# relay-set-d-large-block.net
KiCad netlist of a schematic drawn in EAGLE
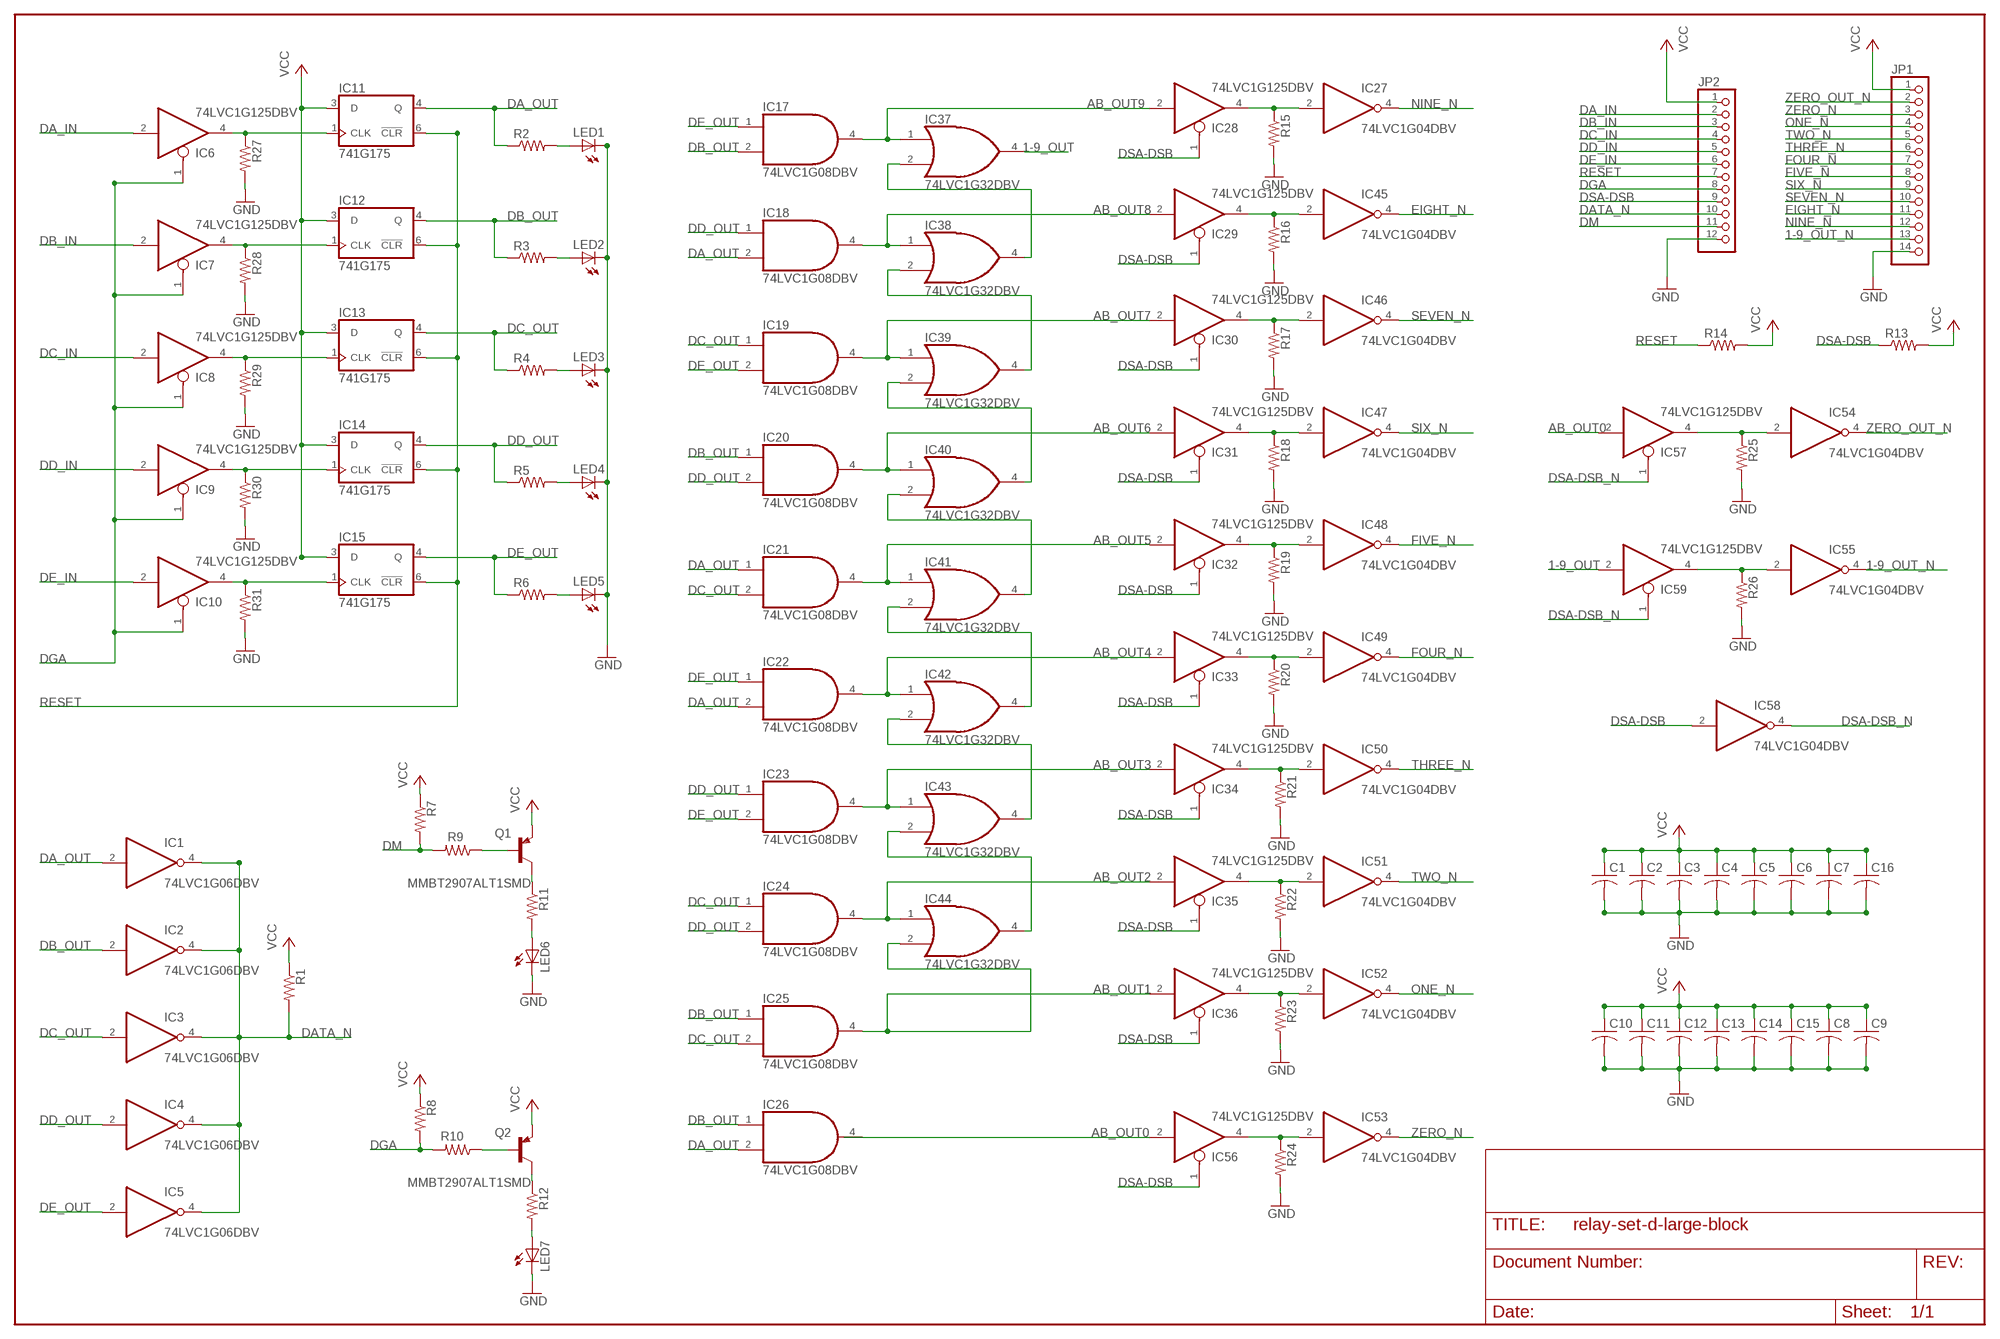
[diagram p0: schematic, sheet 1]

(export (version "E")
  (design (tool "Eeschema 10.0.6"))
  (components
    (comp (ref "C1")
      (value "C-USC0805")
      (footprint "eagle-import:C0805")
      (libsource (lib "eagle-import") (part "C-USC0805"))
    )
    (comp (ref "C2")
      (value "C-USC0805")
      (footprint "eagle-import:C0805")
      (libsource (lib "eagle-import") (part "C-USC0805"))
    )
    (comp (ref "C3")
      (value "C-USC0805")
      (footprint "eagle-import:C0805")
      (libsource (lib "eagle-import") (part "C-USC0805"))
    )
    (comp (ref "C4")
      (value "C-USC0805")
      (footprint "eagle-import:C0805")
      (libsource (lib "eagle-import") (part "C-USC0805"))
    )
    (comp (ref "C5")
      (value "C-USC0805")
      (footprint "eagle-import:C0805")
      (libsource (lib "eagle-import") (part "C-USC0805"))
    )
    (comp (ref "C6")
      (value "C-USC0805")
      (footprint "eagle-import:C0805")
      (libsource (lib "eagle-import") (part "C-USC0805"))
    )
    (comp (ref "C7")
      (value "C-USC0805")
      (footprint "eagle-import:C0805")
      (libsource (lib "eagle-import") (part "C-USC0805"))
    )
    (comp (ref "C8")
      (value "C-USC0805")
      (footprint "eagle-import:C0805")
      (libsource (lib "eagle-import") (part "C-USC0805"))
    )
    (comp (ref "C9")
      (value "C-USC0805")
      (footprint "eagle-import:C0805")
      (libsource (lib "eagle-import") (part "C-USC0805"))
    )
    (comp (ref "C10")
      (value "C-USC0805")
      (footprint "eagle-import:C0805")
      (libsource (lib "eagle-import") (part "C-USC0805"))
    )
    (comp (ref "C11")
      (value "C-USC0805")
      (footprint "eagle-import:C0805")
      (libsource (lib "eagle-import") (part "C-USC0805"))
    )
    (comp (ref "C12")
      (value "C-USC0805")
      (footprint "eagle-import:C0805")
      (libsource (lib "eagle-import") (part "C-USC0805"))
    )
    (comp (ref "C13")
      (value "C-USC0805")
      (footprint "eagle-import:C0805")
      (libsource (lib "eagle-import") (part "C-USC0805"))
    )
    (comp (ref "C14")
      (value "C-USC0805")
      (footprint "eagle-import:C0805")
      (libsource (lib "eagle-import") (part "C-USC0805"))
    )
    (comp (ref "C15")
      (value "C-USC0805")
      (footprint "eagle-import:C0805")
      (libsource (lib "eagle-import") (part "C-USC0805"))
    )
    (comp (ref "C16")
      (value "C-USC0805")
      (footprint "eagle-import:C0805")
      (libsource (lib "eagle-import") (part "C-USC0805"))
    )
    (comp (ref "IC1")
      (value "74LVC1G06DBV")
      (footprint "eagle-import:SOT23-5")
      (libsource (lib "eagle-import") (part "741G06DBVAUC"))
    )
    (comp (ref "IC2")
      (value "74LVC1G06DBV")
      (footprint "eagle-import:SOT23-5")
      (libsource (lib "eagle-import") (part "741G06DBVAUC"))
    )
    (comp (ref "IC3")
      (value "74LVC1G06DBV")
      (footprint "eagle-import:SOT23-5")
      (libsource (lib "eagle-import") (part "741G06DBVAUC"))
    )
    (comp (ref "IC4")
      (value "74LVC1G06DBV")
      (footprint "eagle-import:SOT23-5")
      (libsource (lib "eagle-import") (part "741G06DBVAUC"))
    )
    (comp (ref "IC5")
      (value "74LVC1G06DBV")
      (footprint "eagle-import:SOT23-5")
      (libsource (lib "eagle-import") (part "741G06DBVAUC"))
    )
    (comp (ref "IC6")
      (value "74LVC1G125DBV")
      (footprint "eagle-import:SOT23-5")
      (libsource (lib "eagle-import") (part "741G125DBVLVC"))
    )
    (comp (ref "IC7")
      (value "74LVC1G125DBV")
      (footprint "eagle-import:SOT23-5")
      (libsource (lib "eagle-import") (part "741G125DBVLVC"))
    )
    (comp (ref "IC8")
      (value "74LVC1G125DBV")
      (footprint "eagle-import:SOT23-5")
      (libsource (lib "eagle-import") (part "741G125DBVLVC"))
    )
    (comp (ref "IC9")
      (value "74LVC1G125DBV")
      (footprint "eagle-import:SOT23-5")
      (libsource (lib "eagle-import") (part "741G125DBVLVC"))
    )
    (comp (ref "IC10")
      (value "74LVC1G125DBV")
      (footprint "eagle-import:SOT23-5")
      (libsource (lib "eagle-import") (part "741G125DBVLVC"))
    )
    (comp (ref "IC11")
      (value "741G175")
      (footprint "eagle-import:DBV_R-PDSO-G6")
      (libsource (lib "eagle-import") (part "741G175"))
    )
    (comp (ref "IC12")
      (value "741G175")
      (footprint "eagle-import:DBV_R-PDSO-G6")
      (libsource (lib "eagle-import") (part "741G175"))
    )
    (comp (ref "IC13")
      (value "741G175")
      (footprint "eagle-import:DBV_R-PDSO-G6")
      (libsource (lib "eagle-import") (part "741G175"))
    )
    (comp (ref "IC14")
      (value "741G175")
      (footprint "eagle-import:DBV_R-PDSO-G6")
      (libsource (lib "eagle-import") (part "741G175"))
    )
    (comp (ref "IC15")
      (value "741G175")
      (footprint "eagle-import:DBV_R-PDSO-G6")
      (libsource (lib "eagle-import") (part "741G175"))
    )
    (comp (ref "IC17")
      (value "74LVC1G08DBV")
      (footprint "eagle-import:SOT23-5")
      (libsource (lib "eagle-import") (part "741G08DBVLVC"))
    )
    (comp (ref "IC18")
      (value "74LVC1G08DBV")
      (footprint "eagle-import:SOT23-5")
      (libsource (lib "eagle-import") (part "741G08DBVLVC"))
    )
    (comp (ref "IC19")
      (value "74LVC1G08DBV")
      (footprint "eagle-import:SOT23-5")
      (libsource (lib "eagle-import") (part "741G08DBVLVC"))
    )
    (comp (ref "IC20")
      (value "74LVC1G08DBV")
      (footprint "eagle-import:SOT23-5")
      (libsource (lib "eagle-import") (part "741G08DBVLVC"))
    )
    (comp (ref "IC21")
      (value "74LVC1G08DBV")
      (footprint "eagle-import:SOT23-5")
      (libsource (lib "eagle-import") (part "741G08DBVLVC"))
    )
    (comp (ref "IC22")
      (value "74LVC1G08DBV")
      (footprint "eagle-import:SOT23-5")
      (libsource (lib "eagle-import") (part "741G08DBVLVC"))
    )
    (comp (ref "IC23")
      (value "74LVC1G08DBV")
      (footprint "eagle-import:SOT23-5")
      (libsource (lib "eagle-import") (part "741G08DBVLVC"))
    )
    (comp (ref "IC24")
      (value "74LVC1G08DBV")
      (footprint "eagle-import:SOT23-5")
      (libsource (lib "eagle-import") (part "741G08DBVLVC"))
    )
    (comp (ref "IC25")
      (value "74LVC1G08DBV")
      (footprint "eagle-import:SOT23-5")
      (libsource (lib "eagle-import") (part "741G08DBVLVC"))
    )
    (comp (ref "IC26")
      (value "74LVC1G08DBV")
      (footprint "eagle-import:SOT23-5")
      (libsource (lib "eagle-import") (part "741G08DBVLVC"))
    )
    (comp (ref "IC27")
      (value "74LVC1G04DBV")
      (footprint "eagle-import:SOT23-5")
      (libsource (lib "eagle-import") (part "741G04DBVLVC"))
    )
    (comp (ref "IC28")
      (value "74LVC1G125DBV")
      (footprint "eagle-import:SOT23-5")
      (libsource (lib "eagle-import") (part "741G125DBVLVC"))
    )
    (comp (ref "IC29")
      (value "74LVC1G125DBV")
      (footprint "eagle-import:SOT23-5")
      (libsource (lib "eagle-import") (part "741G125DBVLVC"))
    )
    (comp (ref "IC30")
      (value "74LVC1G125DBV")
      (footprint "eagle-import:SOT23-5")
      (libsource (lib "eagle-import") (part "741G125DBVLVC"))
    )
    (comp (ref "IC31")
      (value "74LVC1G125DBV")
      (footprint "eagle-import:SOT23-5")
      (libsource (lib "eagle-import") (part "741G125DBVLVC"))
    )
    (comp (ref "IC32")
      (value "74LVC1G125DBV")
      (footprint "eagle-import:SOT23-5")
      (libsource (lib "eagle-import") (part "741G125DBVLVC"))
    )
    (comp (ref "IC33")
      (value "74LVC1G125DBV")
      (footprint "eagle-import:SOT23-5")
      (libsource (lib "eagle-import") (part "741G125DBVLVC"))
    )
    (comp (ref "IC34")
      (value "74LVC1G125DBV")
      (footprint "eagle-import:SOT23-5")
      (libsource (lib "eagle-import") (part "741G125DBVLVC"))
    )
    (comp (ref "IC35")
      (value "74LVC1G125DBV")
      (footprint "eagle-import:SOT23-5")
      (libsource (lib "eagle-import") (part "741G125DBVLVC"))
    )
    (comp (ref "IC36")
      (value "74LVC1G125DBV")
      (footprint "eagle-import:SOT23-5")
      (libsource (lib "eagle-import") (part "741G125DBVLVC"))
    )
    (comp (ref "IC37")
      (value "74LVC1G32DBV")
      (footprint "eagle-import:SOT23-5")
      (libsource (lib "eagle-import") (part "741G32DBVAHC"))
    )
    (comp (ref "IC38")
      (value "74LVC1G32DBV")
      (footprint "eagle-import:SOT23-5")
      (libsource (lib "eagle-import") (part "741G32DBVAHC"))
    )
    (comp (ref "IC39")
      (value "74LVC1G32DBV")
      (footprint "eagle-import:SOT23-5")
      (libsource (lib "eagle-import") (part "741G32DBVAHC"))
    )
    (comp (ref "IC40")
      (value "74LVC1G32DBV")
      (footprint "eagle-import:SOT23-5")
      (libsource (lib "eagle-import") (part "741G32DBVAHC"))
    )
    (comp (ref "IC41")
      (value "74LVC1G32DBV")
      (footprint "eagle-import:SOT23-5")
      (libsource (lib "eagle-import") (part "741G32DBVAHC"))
    )
    (comp (ref "IC42")
      (value "74LVC1G32DBV")
      (footprint "eagle-import:SOT23-5")
      (libsource (lib "eagle-import") (part "741G32DBVAHC"))
    )
    (comp (ref "IC43")
      (value "74LVC1G32DBV")
      (footprint "eagle-import:SOT23-5")
      (libsource (lib "eagle-import") (part "741G32DBVAHC"))
    )
    (comp (ref "IC44")
      (value "74LVC1G32DBV")
      (footprint "eagle-import:SOT23-5")
      (libsource (lib "eagle-import") (part "741G32DBVAHC"))
    )
    (comp (ref "IC45")
      (value "74LVC1G04DBV")
      (footprint "eagle-import:SOT23-5")
      (libsource (lib "eagle-import") (part "741G04DBVLVC"))
    )
    (comp (ref "IC46")
      (value "74LVC1G04DBV")
      (footprint "eagle-import:SOT23-5")
      (libsource (lib "eagle-import") (part "741G04DBVLVC"))
    )
    (comp (ref "IC47")
      (value "74LVC1G04DBV")
      (footprint "eagle-import:SOT23-5")
      (libsource (lib "eagle-import") (part "741G04DBVLVC"))
    )
    (comp (ref "IC48")
      (value "74LVC1G04DBV")
      (footprint "eagle-import:SOT23-5")
      (libsource (lib "eagle-import") (part "741G04DBVLVC"))
    )
    (comp (ref "IC49")
      (value "74LVC1G04DBV")
      (footprint "eagle-import:SOT23-5")
      (libsource (lib "eagle-import") (part "741G04DBVLVC"))
    )
    (comp (ref "IC50")
      (value "74LVC1G04DBV")
      (footprint "eagle-import:SOT23-5")
      (libsource (lib "eagle-import") (part "741G04DBVLVC"))
    )
    (comp (ref "IC51")
      (value "74LVC1G04DBV")
      (footprint "eagle-import:SOT23-5")
      (libsource (lib "eagle-import") (part "741G04DBVLVC"))
    )
    (comp (ref "IC52")
      (value "74LVC1G04DBV")
      (footprint "eagle-import:SOT23-5")
      (libsource (lib "eagle-import") (part "741G04DBVLVC"))
    )
    (comp (ref "IC53")
      (value "74LVC1G04DBV")
      (footprint "eagle-import:SOT23-5")
      (libsource (lib "eagle-import") (part "741G04DBVLVC"))
    )
    (comp (ref "IC54")
      (value "74LVC1G04DBV")
      (footprint "eagle-import:SOT23-5")
      (libsource (lib "eagle-import") (part "741G04DBVLVC"))
    )
    (comp (ref "IC55")
      (value "74LVC1G04DBV")
      (footprint "eagle-import:SOT23-5")
      (libsource (lib "eagle-import") (part "741G04DBVLVC"))
    )
    (comp (ref "IC56")
      (value "74LVC1G125DBV")
      (footprint "eagle-import:SOT23-5")
      (libsource (lib "eagle-import") (part "741G125DBVLVC"))
    )
    (comp (ref "IC57")
      (value "74LVC1G125DBV")
      (footprint "eagle-import:SOT23-5")
      (libsource (lib "eagle-import") (part "741G125DBVLVC"))
    )
    (comp (ref "IC58")
      (value "74LVC1G04DBV")
      (footprint "eagle-import:SOT23-5")
      (libsource (lib "eagle-import") (part "741G04DBVLVC"))
    )
    (comp (ref "IC59")
      (value "74LVC1G125DBV")
      (footprint "eagle-import:SOT23-5")
      (libsource (lib "eagle-import") (part "741G125DBVLVC"))
    )
    (comp (ref "JP1")
      (value "PINHD-1X14")
      (footprint "eagle-import:1X14")
      (libsource (lib "eagle-import") (part "PINHD-1X14"))
    )
    (comp (ref "JP2")
      (value "PINHD-1X12")
      (footprint "eagle-import:1X12")
      (libsource (lib "eagle-import") (part "PINHD-1X12"))
    )
    (comp (ref "LED1")
      (value "LEDCHIP-LED0805")
      (footprint "eagle-import:CHIP-LED0805")
      (libsource (lib "eagle-import") (part "LEDCHIP-LED0805"))
    )
    (comp (ref "LED2")
      (value "LEDCHIP-LED0805")
      (footprint "eagle-import:CHIP-LED0805")
      (libsource (lib "eagle-import") (part "LEDCHIP-LED0805"))
    )
    (comp (ref "LED3")
      (value "LEDCHIP-LED0805")
      (footprint "eagle-import:CHIP-LED0805")
      (libsource (lib "eagle-import") (part "LEDCHIP-LED0805"))
    )
    (comp (ref "LED4")
      (value "LEDCHIP-LED0805")
      (footprint "eagle-import:CHIP-LED0805")
      (libsource (lib "eagle-import") (part "LEDCHIP-LED0805"))
    )
    (comp (ref "LED5")
      (value "LEDCHIP-LED0805")
      (footprint "eagle-import:CHIP-LED0805")
      (libsource (lib "eagle-import") (part "LEDCHIP-LED0805"))
    )
    (comp (ref "LED6")
      (value "LEDCHIP-LED0805")
      (footprint "eagle-import:CHIP-LED0805")
      (libsource (lib "eagle-import") (part "LEDCHIP-LED0805"))
    )
    (comp (ref "LED7")
      (value "LEDCHIP-LED0805")
      (footprint "eagle-import:CHIP-LED0805")
      (libsource (lib "eagle-import") (part "LEDCHIP-LED0805"))
    )
    (comp (ref "Q1")
      (value "MMBT2907ALT1SMD")
      (footprint "eagle-import:SOT23-BEC")
      (libsource (lib "eagle-import") (part "MMBT2907SMDALT1"))
    )
    (comp (ref "Q2")
      (value "MMBT2907ALT1SMD")
      (footprint "eagle-import:SOT23-BEC")
      (libsource (lib "eagle-import") (part "MMBT2907SMDALT1"))
    )
    (comp (ref "R1")
      (value "R-US_R0805")
      (footprint "eagle-import:R0805")
      (libsource (lib "eagle-import") (part "R-US_R0805"))
    )
    (comp (ref "R2")
      (value "R-US_R0805")
      (footprint "eagle-import:R0805")
      (libsource (lib "eagle-import") (part "R-US_R0805"))
    )
    (comp (ref "R3")
      (value "R-US_R0805")
      (footprint "eagle-import:R0805")
      (libsource (lib "eagle-import") (part "R-US_R0805"))
    )
    (comp (ref "R4")
      (value "R-US_R0805")
      (footprint "eagle-import:R0805")
      (libsource (lib "eagle-import") (part "R-US_R0805"))
    )
    (comp (ref "R5")
      (value "R-US_R0805")
      (footprint "eagle-import:R0805")
      (libsource (lib "eagle-import") (part "R-US_R0805"))
    )
    (comp (ref "R6")
      (value "R-US_R0805")
      (footprint "eagle-import:R0805")
      (libsource (lib "eagle-import") (part "R-US_R0805"))
    )
    (comp (ref "R7")
      (value "R-US_R0805")
      (footprint "eagle-import:R0805")
      (libsource (lib "eagle-import") (part "R-US_R0805"))
    )
    (comp (ref "R8")
      (value "R-US_R0805")
      (footprint "eagle-import:R0805")
      (libsource (lib "eagle-import") (part "R-US_R0805"))
    )
    (comp (ref "R9")
      (value "R-US_R0805")
      (footprint "eagle-import:R0805")
      (libsource (lib "eagle-import") (part "R-US_R0805"))
    )
    (comp (ref "R10")
      (value "R-US_R0805")
      (footprint "eagle-import:R0805")
      (libsource (lib "eagle-import") (part "R-US_R0805"))
    )
    (comp (ref "R11")
      (value "R-US_R0805")
      (footprint "eagle-import:R0805")
      (libsource (lib "eagle-import") (part "R-US_R0805"))
    )
    (comp (ref "R12")
      (value "R-US_R0805")
      (footprint "eagle-import:R0805")
      (libsource (lib "eagle-import") (part "R-US_R0805"))
    )
    (comp (ref "R13")
      (value "R-US_R0805")
      (footprint "eagle-import:R0805")
      (libsource (lib "eagle-import") (part "R-US_R0805"))
    )
    (comp (ref "R14")
      (value "R-US_R0805")
      (footprint "eagle-import:R0805")
      (libsource (lib "eagle-import") (part "R-US_R0805"))
    )
    (comp (ref "R15")
      (value "R-US_R0805")
      (footprint "eagle-import:R0805")
      (libsource (lib "eagle-import") (part "R-US_R0805"))
    )
    (comp (ref "R16")
      (value "R-US_R0805")
      (footprint "eagle-import:R0805")
      (libsource (lib "eagle-import") (part "R-US_R0805"))
    )
    (comp (ref "R17")
      (value "R-US_R0805")
      (footprint "eagle-import:R0805")
      (libsource (lib "eagle-import") (part "R-US_R0805"))
    )
    (comp (ref "R18")
      (value "R-US_R0805")
      (footprint "eagle-import:R0805")
      (libsource (lib "eagle-import") (part "R-US_R0805"))
    )
    (comp (ref "R19")
      (value "R-US_R0805")
      (footprint "eagle-import:R0805")
      (libsource (lib "eagle-import") (part "R-US_R0805"))
    )
    (comp (ref "R20")
      (value "R-US_R0805")
      (footprint "eagle-import:R0805")
      (libsource (lib "eagle-import") (part "R-US_R0805"))
    )
    (comp (ref "R21")
      (value "R-US_R0805")
      (footprint "eagle-import:R0805")
      (libsource (lib "eagle-import") (part "R-US_R0805"))
    )
    (comp (ref "R22")
      (value "R-US_R0805")
      (footprint "eagle-import:R0805")
      (libsource (lib "eagle-import") (part "R-US_R0805"))
    )
    (comp (ref "R23")
      (value "R-US_R0805")
      (footprint "eagle-import:R0805")
      (libsource (lib "eagle-import") (part "R-US_R0805"))
    )
    (comp (ref "R24")
      (value "R-US_R0805")
      (footprint "eagle-import:R0805")
      (libsource (lib "eagle-import") (part "R-US_R0805"))
    )
    (comp (ref "R25")
      (value "R-US_R0805")
      (footprint "eagle-import:R0805")
      (libsource (lib "eagle-import") (part "R-US_R0805"))
    )
    (comp (ref "R26")
      (value "R-US_R0805")
      (footprint "eagle-import:R0805")
      (libsource (lib "eagle-import") (part "R-US_R0805"))
    )
    (comp (ref "R27")
      (value "R-US_R0805")
      (footprint "eagle-import:R0805")
      (libsource (lib "eagle-import") (part "R-US_R0805"))
    )
    (comp (ref "R28")
      (value "R-US_R0805")
      (footprint "eagle-import:R0805")
      (libsource (lib "eagle-import") (part "R-US_R0805"))
    )
    (comp (ref "R29")
      (value "R-US_R0805")
      (footprint "eagle-import:R0805")
      (libsource (lib "eagle-import") (part "R-US_R0805"))
    )
    (comp (ref "R30")
      (value "R-US_R0805")
      (footprint "eagle-import:R0805")
      (libsource (lib "eagle-import") (part "R-US_R0805"))
    )
    (comp (ref "R31")
      (value "R-US_R0805")
      (footprint "eagle-import:R0805")
      (libsource (lib "eagle-import") (part "R-US_R0805"))
    )
  )
  (nets
    (net (code "1") (name "/1-9_OUT") (class "Default")
      (node (ref "IC37") (pin "4") (pinfunction "O_4") (pintype "output"))
      (node (ref "IC59") (pin "2") (pinfunction "I_2") (pintype "input"))
    )
    (net (code "2") (name "/1-9_OUT_N") (class "Default")
      (node (ref "IC55") (pin "4") (pinfunction "O_4") (pintype "output"))
      (node (ref "JP1") (pin "13") (pinfunction "13_13") (pintype "passive"))
    )
    (net (code "3") (name "/AB_OUT0") (class "Default")
      (node (ref "IC56") (pin "2") (pinfunction "I_2") (pintype "input"))
      (node (ref "IC57") (pin "2") (pinfunction "I_2") (pintype "input"))
    )
    (net (code "4") (name "/AB_OUT1") (class "Default")
      (node (ref "IC25") (pin "4") (pinfunction "O_4") (pintype "output"))
      (node (ref "IC36") (pin "2") (pinfunction "I_2") (pintype "input"))
      (node (ref "IC44") (pin "2") (pinfunction "I1_2") (pintype "input"))
    )
    (net (code "5") (name "/AB_OUT2") (class "Default")
      (node (ref "IC24") (pin "4") (pinfunction "O_4") (pintype "output"))
      (node (ref "IC35") (pin "2") (pinfunction "I_2") (pintype "input"))
      (node (ref "IC44") (pin "1") (pinfunction "I0_1") (pintype "input"))
    )
    (net (code "6") (name "/AB_OUT3") (class "Default")
      (node (ref "IC23") (pin "4") (pinfunction "O_4") (pintype "output"))
      (node (ref "IC34") (pin "2") (pinfunction "I_2") (pintype "input"))
      (node (ref "IC43") (pin "1") (pinfunction "I0_1") (pintype "input"))
    )
    (net (code "7") (name "/AB_OUT4") (class "Default")
      (node (ref "IC22") (pin "4") (pinfunction "O_4") (pintype "output"))
      (node (ref "IC33") (pin "2") (pinfunction "I_2") (pintype "input"))
      (node (ref "IC42") (pin "1") (pinfunction "I0_1") (pintype "input"))
    )
    (net (code "8") (name "/AB_OUT5") (class "Default")
      (node (ref "IC21") (pin "4") (pinfunction "O_4") (pintype "output"))
      (node (ref "IC32") (pin "2") (pinfunction "I_2") (pintype "input"))
      (node (ref "IC41") (pin "1") (pinfunction "I0_1") (pintype "input"))
    )
    (net (code "9") (name "/AB_OUT6") (class "Default")
      (node (ref "IC20") (pin "4") (pinfunction "O_4") (pintype "output"))
      (node (ref "IC31") (pin "2") (pinfunction "I_2") (pintype "input"))
      (node (ref "IC40") (pin "1") (pinfunction "I0_1") (pintype "input"))
    )
    (net (code "10") (name "/AB_OUT7") (class "Default")
      (node (ref "IC19") (pin "4") (pinfunction "O_4") (pintype "output"))
      (node (ref "IC30") (pin "2") (pinfunction "I_2") (pintype "input"))
      (node (ref "IC39") (pin "1") (pinfunction "I0_1") (pintype "input"))
    )
    (net (code "11") (name "/AB_OUT8") (class "Default")
      (node (ref "IC18") (pin "4") (pinfunction "O_4") (pintype "output"))
      (node (ref "IC29") (pin "2") (pinfunction "I_2") (pintype "input"))
      (node (ref "IC38") (pin "1") (pinfunction "I0_1") (pintype "input"))
    )
    (net (code "12") (name "/AB_OUT9") (class "Default")
      (node (ref "IC17") (pin "4") (pinfunction "O_4") (pintype "output"))
      (node (ref "IC28") (pin "2") (pinfunction "I_2") (pintype "input"))
      (node (ref "IC37") (pin "1") (pinfunction "I0_1") (pintype "input"))
    )
    (net (code "13") (name "/DATA_N") (class "Default")
      (node (ref "IC1") (pin "4") (pinfunction "O_4") (pintype "open_collector"))
      (node (ref "IC2") (pin "4") (pinfunction "O_4") (pintype "open_collector"))
      (node (ref "IC3") (pin "4") (pinfunction "O_4") (pintype "open_collector"))
      (node (ref "IC4") (pin "4") (pinfunction "O_4") (pintype "open_collector"))
      (node (ref "IC5") (pin "4") (pinfunction "O_4") (pintype "open_collector"))
      (node (ref "JP2") (pin "10") (pinfunction "10_10") (pintype "passive"))
      (node (ref "R1") (pin "2") (pinfunction "2_2") (pintype "passive"))
    )
    (net (code "14") (name "/DA_IN") (class "Default")
      (node (ref "IC6") (pin "2") (pinfunction "I_2") (pintype "input"))
      (node (ref "JP2") (pin "2") (pinfunction "2_2") (pintype "passive"))
    )
    (net (code "15") (name "/DA_OUT") (class "Default")
      (node (ref "IC1") (pin "2") (pinfunction "I_2") (pintype "input"))
      (node (ref "IC11") (pin "4") (pinfunction "Q_4") (pintype "output"))
      (node (ref "IC18") (pin "2") (pinfunction "I1_2") (pintype "input"))
      (node (ref "IC21") (pin "1") (pinfunction "I0_1") (pintype "input"))
      (node (ref "IC22") (pin "2") (pinfunction "I1_2") (pintype "input"))
      (node (ref "IC26") (pin "2") (pinfunction "I1_2") (pintype "input"))
      (node (ref "R2") (pin "1") (pinfunction "1_1") (pintype "passive"))
    )
    (net (code "16") (name "/DB_IN") (class "Default")
      (node (ref "IC7") (pin "2") (pinfunction "I_2") (pintype "input"))
      (node (ref "JP2") (pin "3") (pinfunction "3_3") (pintype "passive"))
    )
    (net (code "17") (name "/DB_OUT") (class "Default")
      (node (ref "IC12") (pin "4") (pinfunction "Q_4") (pintype "output"))
      (node (ref "IC17") (pin "2") (pinfunction "I1_2") (pintype "input"))
      (node (ref "IC2") (pin "2") (pinfunction "I_2") (pintype "input"))
      (node (ref "IC20") (pin "1") (pinfunction "I0_1") (pintype "input"))
      (node (ref "IC25") (pin "1") (pinfunction "I0_1") (pintype "input"))
      (node (ref "IC26") (pin "1") (pinfunction "I0_1") (pintype "input"))
      (node (ref "R3") (pin "1") (pinfunction "1_1") (pintype "passive"))
    )
    (net (code "18") (name "/DC_IN") (class "Default")
      (node (ref "IC8") (pin "2") (pinfunction "I_2") (pintype "input"))
      (node (ref "JP2") (pin "4") (pinfunction "4_4") (pintype "passive"))
    )
    (net (code "19") (name "/DC_OUT") (class "Default")
      (node (ref "IC13") (pin "4") (pinfunction "Q_4") (pintype "output"))
      (node (ref "IC19") (pin "1") (pinfunction "I0_1") (pintype "input"))
      (node (ref "IC21") (pin "2") (pinfunction "I1_2") (pintype "input"))
      (node (ref "IC24") (pin "1") (pinfunction "I0_1") (pintype "input"))
      (node (ref "IC25") (pin "2") (pinfunction "I1_2") (pintype "input"))
      (node (ref "IC3") (pin "2") (pinfunction "I_2") (pintype "input"))
      (node (ref "R4") (pin "1") (pinfunction "1_1") (pintype "passive"))
    )
    (net (code "20") (name "/DD_IN") (class "Default")
      (node (ref "IC9") (pin "2") (pinfunction "I_2") (pintype "input"))
      (node (ref "JP2") (pin "5") (pinfunction "5_5") (pintype "passive"))
    )
    (net (code "21") (name "/DD_OUT") (class "Default")
      (node (ref "IC14") (pin "4") (pinfunction "Q_4") (pintype "output"))
      (node (ref "IC18") (pin "1") (pinfunction "I0_1") (pintype "input"))
      (node (ref "IC20") (pin "2") (pinfunction "I1_2") (pintype "input"))
      (node (ref "IC23") (pin "1") (pinfunction "I0_1") (pintype "input"))
      (node (ref "IC24") (pin "2") (pinfunction "I1_2") (pintype "input"))
      (node (ref "IC4") (pin "2") (pinfunction "I_2") (pintype "input"))
      (node (ref "R5") (pin "1") (pinfunction "1_1") (pintype "passive"))
    )
    (net (code "22") (name "/DE_IN") (class "Default")
      (node (ref "IC10") (pin "2") (pinfunction "I_2") (pintype "input"))
      (node (ref "JP2") (pin "6") (pinfunction "6_6") (pintype "passive"))
    )
    (net (code "23") (name "/DE_OUT") (class "Default")
      (node (ref "IC15") (pin "4") (pinfunction "Q_4") (pintype "output"))
      (node (ref "IC17") (pin "1") (pinfunction "I0_1") (pintype "input"))
      (node (ref "IC19") (pin "2") (pinfunction "I1_2") (pintype "input"))
      (node (ref "IC22") (pin "1") (pinfunction "I0_1") (pintype "input"))
      (node (ref "IC23") (pin "2") (pinfunction "I1_2") (pintype "input"))
      (node (ref "IC5") (pin "2") (pinfunction "I_2") (pintype "input"))
      (node (ref "R6") (pin "1") (pinfunction "1_1") (pintype "passive"))
    )
    (net (code "24") (name "/DGA") (class "Default")
      (node (ref "IC10") (pin "1") (pinfunction "OE_1") (pintype "input"))
      (node (ref "IC6") (pin "1") (pinfunction "OE_1") (pintype "input"))
      (node (ref "IC7") (pin "1") (pinfunction "OE_1") (pintype "input"))
      (node (ref "IC8") (pin "1") (pinfunction "OE_1") (pintype "input"))
      (node (ref "IC9") (pin "1") (pinfunction "OE_1") (pintype "input"))
      (node (ref "JP2") (pin "8") (pinfunction "8_8") (pintype "passive"))
      (node (ref "R10") (pin "2") (pinfunction "2_2") (pintype "passive"))
      (node (ref "R8") (pin "2") (pinfunction "2_2") (pintype "passive"))
    )
    (net (code "25") (name "/DM") (class "Default")
      (node (ref "JP2") (pin "11") (pinfunction "11_11") (pintype "passive"))
      (node (ref "R7") (pin "2") (pinfunction "2_2") (pintype "passive"))
      (node (ref "R9") (pin "2") (pinfunction "2_2") (pintype "passive"))
    )
    (net (code "26") (name "/DSA-DSB") (class "Default")
      (node (ref "IC28") (pin "1") (pinfunction "OE_1") (pintype "input"))
      (node (ref "IC29") (pin "1") (pinfunction "OE_1") (pintype "input"))
      (node (ref "IC30") (pin "1") (pinfunction "OE_1") (pintype "input"))
      (node (ref "IC31") (pin "1") (pinfunction "OE_1") (pintype "input"))
      (node (ref "IC32") (pin "1") (pinfunction "OE_1") (pintype "input"))
      (node (ref "IC33") (pin "1") (pinfunction "OE_1") (pintype "input"))
      (node (ref "IC34") (pin "1") (pinfunction "OE_1") (pintype "input"))
      (node (ref "IC35") (pin "1") (pinfunction "OE_1") (pintype "input"))
      (node (ref "IC36") (pin "1") (pinfunction "OE_1") (pintype "input"))
      (node (ref "IC56") (pin "1") (pinfunction "OE_1") (pintype "input"))
      (node (ref "IC58") (pin "2") (pinfunction "I_2") (pintype "input"))
      (node (ref "JP2") (pin "9") (pinfunction "9_9") (pintype "passive"))
      (node (ref "R13") (pin "1") (pinfunction "1_1") (pintype "passive"))
    )
    (net (code "27") (name "/DSA-DSB_N") (class "Default")
      (node (ref "IC57") (pin "1") (pinfunction "OE_1") (pintype "input"))
      (node (ref "IC58") (pin "4") (pinfunction "O_4") (pintype "output"))
      (node (ref "IC59") (pin "1") (pinfunction "OE_1") (pintype "input"))
    )
    (net (code "28") (name "/EIGHT_N") (class "Default")
      (node (ref "IC45") (pin "4") (pinfunction "O_4") (pintype "output"))
      (node (ref "JP1") (pin "11") (pinfunction "11_11") (pintype "passive"))
    )
    (net (code "29") (name "/FIVE_N") (class "Default")
      (node (ref "IC48") (pin "4") (pinfunction "O_4") (pintype "output"))
      (node (ref "JP1") (pin "8") (pinfunction "8_8") (pintype "passive"))
    )
    (net (code "30") (name "/FOUR_N") (class "Default")
      (node (ref "IC49") (pin "4") (pinfunction "O_4") (pintype "output"))
      (node (ref "JP1") (pin "7") (pinfunction "7_7") (pintype "passive"))
    )
    (net (code "31") (name "/NINE_N") (class "Default")
      (node (ref "IC27") (pin "4") (pinfunction "O_4") (pintype "output"))
      (node (ref "JP1") (pin "12") (pinfunction "12_12") (pintype "passive"))
    )
    (net (code "32") (name "/ONE_N") (class "Default")
      (node (ref "IC52") (pin "4") (pinfunction "O_4") (pintype "output"))
      (node (ref "JP1") (pin "4") (pinfunction "4_4") (pintype "passive"))
    )
    (net (code "33") (name "/RESET") (class "Default")
      (node (ref "IC11") (pin "6") (pinfunction "~{CLR}_6") (pintype "output"))
      (node (ref "IC12") (pin "6") (pinfunction "~{CLR}_6") (pintype "output"))
      (node (ref "IC13") (pin "6") (pinfunction "~{CLR}_6") (pintype "output"))
      (node (ref "IC14") (pin "6") (pinfunction "~{CLR}_6") (pintype "output"))
      (node (ref "IC15") (pin "6") (pinfunction "~{CLR}_6") (pintype "output"))
      (node (ref "JP2") (pin "7") (pinfunction "7_7") (pintype "passive"))
      (node (ref "R14") (pin "1") (pinfunction "1_1") (pintype "passive"))
    )
    (net (code "34") (name "/SEVEN_N") (class "Default")
      (node (ref "IC46") (pin "4") (pinfunction "O_4") (pintype "output"))
      (node (ref "JP1") (pin "10") (pinfunction "10_10") (pintype "passive"))
    )
    (net (code "35") (name "/SIX_N") (class "Default")
      (node (ref "IC47") (pin "4") (pinfunction "O_4") (pintype "output"))
      (node (ref "JP1") (pin "9") (pinfunction "9_9") (pintype "passive"))
    )
    (net (code "36") (name "/THREE_N") (class "Default")
      (node (ref "IC50") (pin "4") (pinfunction "O_4") (pintype "output"))
      (node (ref "JP1") (pin "6") (pinfunction "6_6") (pintype "passive"))
    )
    (net (code "37") (name "/TWO_N") (class "Default")
      (node (ref "IC51") (pin "4") (pinfunction "O_4") (pintype "output"))
      (node (ref "JP1") (pin "5") (pinfunction "5_5") (pintype "passive"))
    )
    (net (code "38") (name "/ZERO_N") (class "Default")
      (node (ref "IC53") (pin "4") (pinfunction "O_4") (pintype "output"))
      (node (ref "JP1") (pin "3") (pinfunction "3_3") (pintype "passive"))
    )
    (net (code "39") (name "/ZERO_OUT_N") (class "Default")
      (node (ref "IC54") (pin "4") (pinfunction "O_4") (pintype "output"))
      (node (ref "JP1") (pin "2") (pinfunction "2_2") (pintype "passive"))
    )
    (net (code "40") (name "GND") (class "Default")
      (node (ref "C1") (pin "2") (pinfunction "2_2") (pintype "passive"))
      (node (ref "C10") (pin "2") (pinfunction "2_2") (pintype "passive"))
      (node (ref "C11") (pin "2") (pinfunction "2_2") (pintype "passive"))
      (node (ref "C12") (pin "2") (pinfunction "2_2") (pintype "passive"))
      (node (ref "C13") (pin "2") (pinfunction "2_2") (pintype "passive"))
      (node (ref "C14") (pin "2") (pinfunction "2_2") (pintype "passive"))
      (node (ref "C15") (pin "2") (pinfunction "2_2") (pintype "passive"))
      (node (ref "C16") (pin "2") (pinfunction "2_2") (pintype "passive"))
      (node (ref "C2") (pin "2") (pinfunction "2_2") (pintype "passive"))
      (node (ref "C3") (pin "2") (pinfunction "2_2") (pintype "passive"))
      (node (ref "C4") (pin "2") (pinfunction "2_2") (pintype "passive"))
      (node (ref "C5") (pin "2") (pinfunction "2_2") (pintype "passive"))
      (node (ref "C6") (pin "2") (pinfunction "2_2") (pintype "passive"))
      (node (ref "C7") (pin "2") (pinfunction "2_2") (pintype "passive"))
      (node (ref "C8") (pin "2") (pinfunction "2_2") (pintype "passive"))
      (node (ref "C9") (pin "2") (pinfunction "2_2") (pintype "passive"))
      (node (ref "JP1") (pin "14") (pinfunction "14_14") (pintype "passive"))
      (node (ref "JP2") (pin "12") (pinfunction "12_12") (pintype "passive"))
      (node (ref "LED1") (pin "C") (pinfunction "C_C") (pintype "passive"))
      (node (ref "LED2") (pin "C") (pinfunction "C_C") (pintype "passive"))
      (node (ref "LED3") (pin "C") (pinfunction "C_C") (pintype "passive"))
      (node (ref "LED4") (pin "C") (pinfunction "C_C") (pintype "passive"))
      (node (ref "LED5") (pin "C") (pinfunction "C_C") (pintype "passive"))
      (node (ref "LED6") (pin "C") (pinfunction "C_C") (pintype "passive"))
      (node (ref "LED7") (pin "C") (pinfunction "C_C") (pintype "passive"))
      (node (ref "R15") (pin "2") (pinfunction "2_2") (pintype "passive"))
      (node (ref "R16") (pin "2") (pinfunction "2_2") (pintype "passive"))
      (node (ref "R17") (pin "2") (pinfunction "2_2") (pintype "passive"))
      (node (ref "R18") (pin "2") (pinfunction "2_2") (pintype "passive"))
      (node (ref "R19") (pin "2") (pinfunction "2_2") (pintype "passive"))
      (node (ref "R20") (pin "2") (pinfunction "2_2") (pintype "passive"))
      (node (ref "R21") (pin "2") (pinfunction "2_2") (pintype "passive"))
      (node (ref "R22") (pin "2") (pinfunction "2_2") (pintype "passive"))
      (node (ref "R23") (pin "2") (pinfunction "2_2") (pintype "passive"))
      (node (ref "R24") (pin "2") (pinfunction "2_2") (pintype "passive"))
      (node (ref "R25") (pin "2") (pinfunction "2_2") (pintype "passive"))
      (node (ref "R26") (pin "2") (pinfunction "2_2") (pintype "passive"))
      (node (ref "R27") (pin "2") (pinfunction "2_2") (pintype "passive"))
      (node (ref "R28") (pin "2") (pinfunction "2_2") (pintype "passive"))
      (node (ref "R29") (pin "2") (pinfunction "2_2") (pintype "passive"))
      (node (ref "R30") (pin "2") (pinfunction "2_2") (pintype "passive"))
      (node (ref "R31") (pin "2") (pinfunction "2_2") (pintype "passive"))
    )
    (net (code "41") (name "Net-(IC10A-O)") (class "Default")
      (node (ref "IC10") (pin "4") (pinfunction "O_4") (pintype "tri_state"))
      (node (ref "IC15") (pin "1") (pinfunction "CLK_1") (pintype "input"))
      (node (ref "R31") (pin "1") (pinfunction "1_1") (pintype "passive"))
    )
    (net (code "42") (name "Net-(IC11A-CLK)") (class "Default")
      (node (ref "IC11") (pin "1") (pinfunction "CLK_1") (pintype "input"))
      (node (ref "IC6") (pin "4") (pinfunction "O_4") (pintype "tri_state"))
      (node (ref "R27") (pin "1") (pinfunction "1_1") (pintype "passive"))
    )
    (net (code "43") (name "Net-(IC12A-CLK)") (class "Default")
      (node (ref "IC12") (pin "1") (pinfunction "CLK_1") (pintype "input"))
      (node (ref "IC7") (pin "4") (pinfunction "O_4") (pintype "tri_state"))
      (node (ref "R28") (pin "1") (pinfunction "1_1") (pintype "passive"))
    )
    (net (code "44") (name "Net-(IC13A-CLK)") (class "Default")
      (node (ref "IC13") (pin "1") (pinfunction "CLK_1") (pintype "input"))
      (node (ref "IC8") (pin "4") (pinfunction "O_4") (pintype "tri_state"))
      (node (ref "R29") (pin "1") (pinfunction "1_1") (pintype "passive"))
    )
    (net (code "45") (name "Net-(IC14A-CLK)") (class "Default")
      (node (ref "IC14") (pin "1") (pinfunction "CLK_1") (pintype "input"))
      (node (ref "IC9") (pin "4") (pinfunction "O_4") (pintype "tri_state"))
      (node (ref "R30") (pin "1") (pinfunction "1_1") (pintype "passive"))
    )
    (net (code "46") (name "Net-(IC27A-I)") (class "Default")
      (node (ref "IC27") (pin "2") (pinfunction "I_2") (pintype "input"))
      (node (ref "IC28") (pin "4") (pinfunction "O_4") (pintype "tri_state"))
      (node (ref "R15") (pin "1") (pinfunction "1_1") (pintype "passive"))
    )
    (net (code "47") (name "Net-(IC29A-O)") (class "Default")
      (node (ref "IC29") (pin "4") (pinfunction "O_4") (pintype "tri_state"))
      (node (ref "IC45") (pin "2") (pinfunction "I_2") (pintype "input"))
      (node (ref "R16") (pin "1") (pinfunction "1_1") (pintype "passive"))
    )
    (net (code "48") (name "Net-(IC30A-O)") (class "Default")
      (node (ref "IC30") (pin "4") (pinfunction "O_4") (pintype "tri_state"))
      (node (ref "IC46") (pin "2") (pinfunction "I_2") (pintype "input"))
      (node (ref "R17") (pin "1") (pinfunction "1_1") (pintype "passive"))
    )
    (net (code "49") (name "Net-(IC31A-O)") (class "Default")
      (node (ref "IC31") (pin "4") (pinfunction "O_4") (pintype "tri_state"))
      (node (ref "IC47") (pin "2") (pinfunction "I_2") (pintype "input"))
      (node (ref "R18") (pin "1") (pinfunction "1_1") (pintype "passive"))
    )
    (net (code "50") (name "Net-(IC32A-O)") (class "Default")
      (node (ref "IC32") (pin "4") (pinfunction "O_4") (pintype "tri_state"))
      (node (ref "IC48") (pin "2") (pinfunction "I_2") (pintype "input"))
      (node (ref "R19") (pin "1") (pinfunction "1_1") (pintype "passive"))
    )
    (net (code "51") (name "Net-(IC33A-O)") (class "Default")
      (node (ref "IC33") (pin "4") (pinfunction "O_4") (pintype "tri_state"))
      (node (ref "IC49") (pin "2") (pinfunction "I_2") (pintype "input"))
      (node (ref "R20") (pin "1") (pinfunction "1_1") (pintype "passive"))
    )
    (net (code "52") (name "Net-(IC34A-O)") (class "Default")
      (node (ref "IC34") (pin "4") (pinfunction "O_4") (pintype "tri_state"))
      (node (ref "IC50") (pin "2") (pinfunction "I_2") (pintype "input"))
      (node (ref "R21") (pin "1") (pinfunction "1_1") (pintype "passive"))
    )
    (net (code "53") (name "Net-(IC35A-O)") (class "Default")
      (node (ref "IC35") (pin "4") (pinfunction "O_4") (pintype "tri_state"))
      (node (ref "IC51") (pin "2") (pinfunction "I_2") (pintype "input"))
      (node (ref "R22") (pin "1") (pinfunction "1_1") (pintype "passive"))
    )
    (net (code "54") (name "Net-(IC36A-O)") (class "Default")
      (node (ref "IC36") (pin "4") (pinfunction "O_4") (pintype "tri_state"))
      (node (ref "IC52") (pin "2") (pinfunction "I_2") (pintype "input"))
      (node (ref "R23") (pin "1") (pinfunction "1_1") (pintype "passive"))
    )
    (net (code "55") (name "Net-(IC37A-I1)") (class "Default")
      (node (ref "IC37") (pin "2") (pinfunction "I1_2") (pintype "input"))
      (node (ref "IC38") (pin "4") (pinfunction "O_4") (pintype "output"))
    )
    (net (code "56") (name "Net-(IC38A-I1)") (class "Default")
      (node (ref "IC38") (pin "2") (pinfunction "I1_2") (pintype "input"))
      (node (ref "IC39") (pin "4") (pinfunction "O_4") (pintype "output"))
    )
    (net (code "57") (name "Net-(IC39A-I1)") (class "Default")
      (node (ref "IC39") (pin "2") (pinfunction "I1_2") (pintype "input"))
      (node (ref "IC40") (pin "4") (pinfunction "O_4") (pintype "output"))
    )
    (net (code "58") (name "Net-(IC40A-I1)") (class "Default")
      (node (ref "IC40") (pin "2") (pinfunction "I1_2") (pintype "input"))
      (node (ref "IC41") (pin "4") (pinfunction "O_4") (pintype "output"))
    )
    (net (code "59") (name "Net-(IC41A-I1)") (class "Default")
      (node (ref "IC41") (pin "2") (pinfunction "I1_2") (pintype "input"))
      (node (ref "IC42") (pin "4") (pinfunction "O_4") (pintype "output"))
    )
    (net (code "60") (name "Net-(IC42A-I1)") (class "Default")
      (node (ref "IC42") (pin "2") (pinfunction "I1_2") (pintype "input"))
      (node (ref "IC43") (pin "4") (pinfunction "O_4") (pintype "output"))
    )
    (net (code "61") (name "Net-(IC43A-I1)") (class "Default")
      (node (ref "IC43") (pin "2") (pinfunction "I1_2") (pintype "input"))
      (node (ref "IC44") (pin "4") (pinfunction "O_4") (pintype "output"))
    )
    (net (code "62") (name "Net-(IC53A-I)") (class "Default")
      (node (ref "IC53") (pin "2") (pinfunction "I_2") (pintype "input"))
      (node (ref "IC56") (pin "4") (pinfunction "O_4") (pintype "tri_state"))
      (node (ref "R24") (pin "1") (pinfunction "1_1") (pintype "passive"))
    )
    (net (code "63") (name "Net-(IC54A-I)") (class "Default")
      (node (ref "IC54") (pin "2") (pinfunction "I_2") (pintype "input"))
      (node (ref "IC57") (pin "4") (pinfunction "O_4") (pintype "tri_state"))
      (node (ref "R25") (pin "1") (pinfunction "1_1") (pintype "passive"))
    )
    (net (code "64") (name "Net-(IC55A-I)") (class "Default")
      (node (ref "IC55") (pin "2") (pinfunction "I_2") (pintype "input"))
      (node (ref "IC59") (pin "4") (pinfunction "O_4") (pintype "tri_state"))
      (node (ref "R26") (pin "1") (pinfunction "1_1") (pintype "passive"))
    )
    (net (code "65") (name "Net-(LED1-PadA)") (class "Default")
      (node (ref "LED1") (pin "A") (pinfunction "A_A") (pintype "passive"))
      (node (ref "R2") (pin "2") (pinfunction "2_2") (pintype "passive"))
    )
    (net (code "66") (name "Net-(LED2-PadA)") (class "Default")
      (node (ref "LED2") (pin "A") (pinfunction "A_A") (pintype "passive"))
      (node (ref "R3") (pin "2") (pinfunction "2_2") (pintype "passive"))
    )
    (net (code "67") (name "Net-(LED3-PadA)") (class "Default")
      (node (ref "LED3") (pin "A") (pinfunction "A_A") (pintype "passive"))
      (node (ref "R4") (pin "2") (pinfunction "2_2") (pintype "passive"))
    )
    (net (code "68") (name "Net-(LED4-PadA)") (class "Default")
      (node (ref "LED4") (pin "A") (pinfunction "A_A") (pintype "passive"))
      (node (ref "R5") (pin "2") (pinfunction "2_2") (pintype "passive"))
    )
    (net (code "69") (name "Net-(LED5-PadA)") (class "Default")
      (node (ref "LED5") (pin "A") (pinfunction "A_A") (pintype "passive"))
      (node (ref "R6") (pin "2") (pinfunction "2_2") (pintype "passive"))
    )
    (net (code "70") (name "Net-(LED6-PadA)") (class "Default")
      (node (ref "LED6") (pin "A") (pinfunction "A_A") (pintype "passive"))
      (node (ref "R11") (pin "2") (pinfunction "2_2") (pintype "passive"))
    )
    (net (code "71") (name "Net-(LED7-PadA)") (class "Default")
      (node (ref "LED7") (pin "A") (pinfunction "A_A") (pintype "passive"))
      (node (ref "R12") (pin "2") (pinfunction "2_2") (pintype "passive"))
    )
    (net (code "72") (name "Net-(Q1-PadB)") (class "Default")
      (node (ref "Q1") (pin "B") (pinfunction "B_B") (pintype "passive"))
      (node (ref "R9") (pin "1") (pinfunction "1_1") (pintype "passive"))
    )
    (net (code "73") (name "Net-(Q1-PadC)") (class "Default")
      (node (ref "Q1") (pin "C") (pinfunction "C_C") (pintype "passive"))
      (node (ref "R11") (pin "1") (pinfunction "1_1") (pintype "passive"))
    )
    (net (code "74") (name "Net-(Q2-PadB)") (class "Default")
      (node (ref "Q2") (pin "B") (pinfunction "B_B") (pintype "passive"))
      (node (ref "R10") (pin "1") (pinfunction "1_1") (pintype "passive"))
    )
    (net (code "75") (name "Net-(Q2-PadC)") (class "Default")
      (node (ref "Q2") (pin "C") (pinfunction "C_C") (pintype "passive"))
      (node (ref "R12") (pin "1") (pinfunction "1_1") (pintype "passive"))
    )
    (net (code "76") (name "VCC") (class "Default")
      (node (ref "C1") (pin "1") (pinfunction "1_1") (pintype "passive"))
      (node (ref "C10") (pin "1") (pinfunction "1_1") (pintype "passive"))
      (node (ref "C11") (pin "1") (pinfunction "1_1") (pintype "passive"))
      (node (ref "C12") (pin "1") (pinfunction "1_1") (pintype "passive"))
      (node (ref "C13") (pin "1") (pinfunction "1_1") (pintype "passive"))
      (node (ref "C14") (pin "1") (pinfunction "1_1") (pintype "passive"))
      (node (ref "C15") (pin "1") (pinfunction "1_1") (pintype "passive"))
      (node (ref "C16") (pin "1") (pinfunction "1_1") (pintype "passive"))
      (node (ref "C2") (pin "1") (pinfunction "1_1") (pintype "passive"))
      (node (ref "C3") (pin "1") (pinfunction "1_1") (pintype "passive"))
      (node (ref "C4") (pin "1") (pinfunction "1_1") (pintype "passive"))
      (node (ref "C5") (pin "1") (pinfunction "1_1") (pintype "passive"))
      (node (ref "C6") (pin "1") (pinfunction "1_1") (pintype "passive"))
      (node (ref "C7") (pin "1") (pinfunction "1_1") (pintype "passive"))
      (node (ref "C8") (pin "1") (pinfunction "1_1") (pintype "passive"))
      (node (ref "C9") (pin "1") (pinfunction "1_1") (pintype "passive"))
      (node (ref "IC11") (pin "3") (pinfunction "D_3") (pintype "input"))
      (node (ref "IC12") (pin "3") (pinfunction "D_3") (pintype "input"))
      (node (ref "IC13") (pin "3") (pinfunction "D_3") (pintype "input"))
      (node (ref "IC14") (pin "3") (pinfunction "D_3") (pintype "input"))
      (node (ref "IC15") (pin "3") (pinfunction "D_3") (pintype "input"))
      (node (ref "JP1") (pin "1") (pinfunction "1_1") (pintype "passive"))
      (node (ref "JP2") (pin "1") (pinfunction "1_1") (pintype "passive"))
      (node (ref "Q1") (pin "E") (pinfunction "E_E") (pintype "passive"))
      (node (ref "Q2") (pin "E") (pinfunction "E_E") (pintype "passive"))
      (node (ref "R1") (pin "1") (pinfunction "1_1") (pintype "passive"))
      (node (ref "R13") (pin "2") (pinfunction "2_2") (pintype "passive"))
      (node (ref "R14") (pin "2") (pinfunction "2_2") (pintype "passive"))
      (node (ref "R7") (pin "1") (pinfunction "1_1") (pintype "passive"))
      (node (ref "R8") (pin "1") (pinfunction "1_1") (pintype "passive"))
    )
    (net (code "77") (name "unconnected-(IC26A-O-Pad4)") (class "Default")
      (node (ref "IC26") (pin "4") (pinfunction "O_4") (pintype "output"))
    )
  )
)
